# RF_Glow_Stick.net
KiCad netlist of a schematic drawn in EAGLE
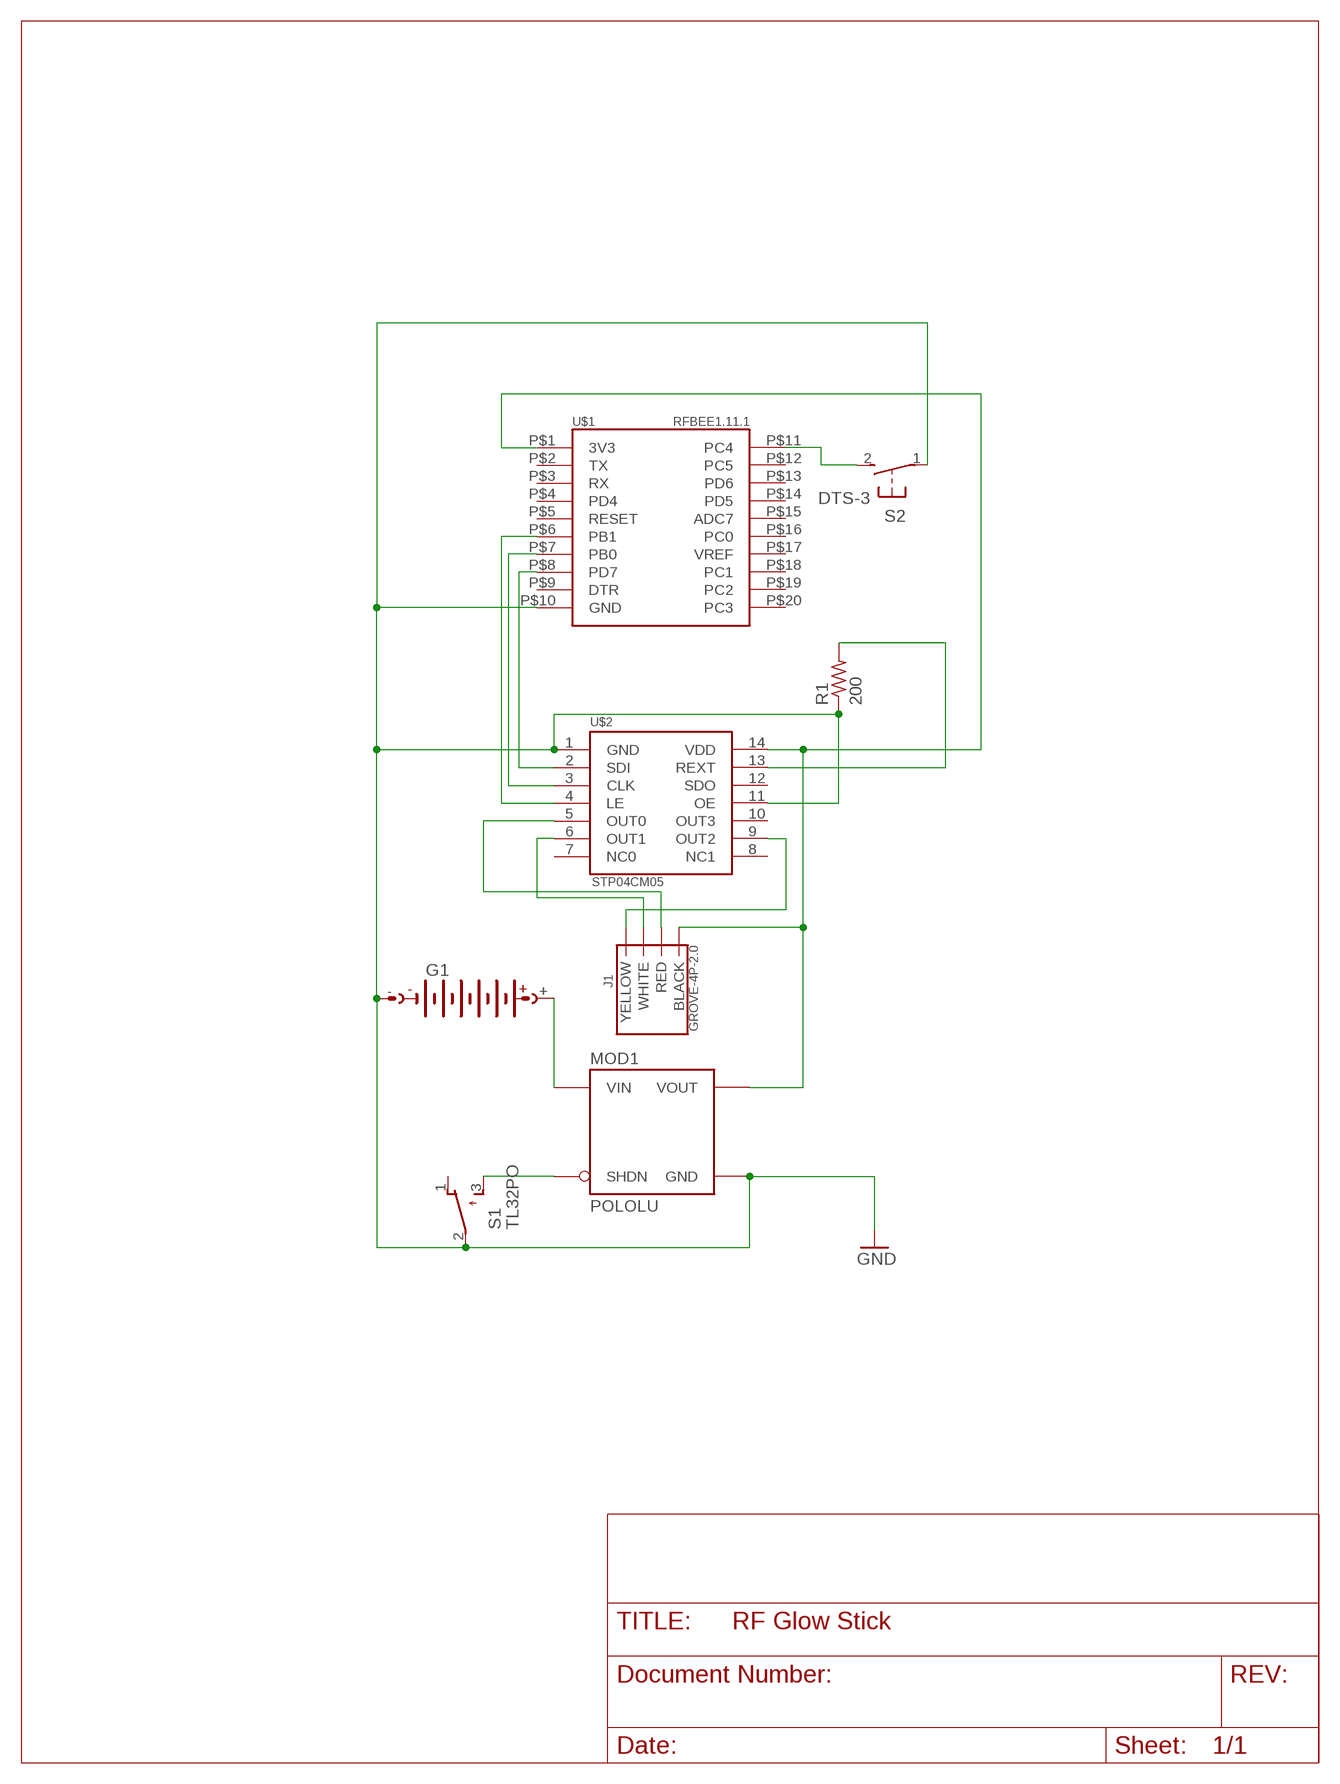
[diagram p0: schematic, sheet 1]

(export (version "E")
  (design (tool "Eeschema 10.0.6"))
  (components
    (comp (ref "G1")
      (value "AB9V")
      (footprint "eagle-import:AB9V")
      (libsource (lib "eagle-import") (part "AB9V"))
    )
    (comp (ref "J1")
      (value "GROVE-4P-2.0")
      (footprint "eagle-import:4P-2.0-90D")
      (libsource (lib "eagle-import") (part "GROVE-4P-2.0"))
    )
    (comp (ref "MOD1")
      (value "POLOLU")
      (footprint "eagle-import:POLOLU_REG09B")
      (libsource (lib "eagle-import") (part "POLOLU_REG09BV"))
    )
    (comp (ref "R1")
      (value "200")
      (footprint "eagle-import:0309_12")
      (libsource (lib "eagle-import") (part "R-US_0309/12"))
    )
    (comp (ref "S1")
      (value "TL32PO")
      (footprint "eagle-import:TL3XPO")
      (libsource (lib "eagle-import") (part "TL32PO"))
    )
    (comp (ref "S2")
      (value "DTS-3")
      (footprint "eagle-import:DTS-3")
      (libsource (lib "eagle-import") (part "DTS-3"))
    )
    (comp (ref "U$1")
      (value "RFBEE1.11.1")
      (footprint "eagle-import:RFBEE")
      (libsource (lib "eagle-import") (part "RFBEE1.11.1"))
    )
    (comp (ref "U$2")
      (value "STP04CM05")
      (footprint "eagle-import:DIL14")
      (libsource (lib "eagle-import") (part "STP04CM05STP04CM05"))
    )
  )
  (nets
    (net (code "1") (name "GND") (class "Default")
      (node (ref "G1") (pin "-") (pinfunction "-_-") (pintype "passive"))
      (node (ref "MOD1") (pin "G") (pinfunction "GND_G") (pintype "power_in"))
      (node (ref "R1") (pin "1") (pinfunction "1_1") (pintype "passive"))
      (node (ref "S1") (pin "2") (pinfunction "P_2") (pintype "passive"))
      (node (ref "S2") (pin "1") (pinfunction "1_1") (pintype "passive"))
      (node (ref "U$1") (pin "P$10") (pinfunction "GND_P$10") (pintype "bidirectional"))
      (node (ref "U$2") (pin "1") (pinfunction "GND_1") (pintype "bidirectional"))
      (node (ref "U$2") (pin "11") (pinfunction "OE_11") (pintype "bidirectional"))
    )
    (net (code "2") (name "Net-(MOD1-SHDN)") (class "Default")
      (node (ref "MOD1") (pin "S") (pinfunction "SHDN_S") (pintype "input"))
      (node (ref "S1") (pin "3") (pinfunction "S_3") (pintype "passive"))
    )
    (net (code "3") (name "Net-(MOD1-VIN)") (class "Default")
      (node (ref "G1") (pin "+") (pinfunction "+_+") (pintype "passive"))
      (node (ref "MOD1") (pin "I") (pinfunction "VIN_I") (pintype "power_in"))
    )
    (net (code "4") (name "Net-(MOD1-VOUT)") (class "Default")
      (node (ref "J1") (pin "BLACK") (pinfunction "BLACK_BLACK") (pintype "bidirectional"))
      (node (ref "MOD1") (pin "O") (pinfunction "VOUT_O") (pintype "output"))
      (node (ref "U$1") (pin "P$1") (pinfunction "3V3_P$1") (pintype "bidirectional"))
      (node (ref "U$2") (pin "14") (pinfunction "VDD_14") (pintype "bidirectional"))
    )
    (net (code "5") (name "Net-(U$1-PB0)") (class "Default")
      (node (ref "U$1") (pin "P$7") (pinfunction "PB0_P$7") (pintype "bidirectional"))
      (node (ref "U$2") (pin "3") (pinfunction "CLK_3") (pintype "bidirectional"))
    )
    (net (code "6") (name "Net-(U$1-PB1)") (class "Default")
      (node (ref "U$1") (pin "P$6") (pinfunction "PB1_P$6") (pintype "bidirectional"))
      (node (ref "U$2") (pin "4") (pinfunction "LE_4") (pintype "bidirectional"))
    )
    (net (code "7") (name "Net-(U$1-PC4)") (class "Default")
      (node (ref "S2") (pin "2") (pinfunction "2_2") (pintype "passive"))
      (node (ref "U$1") (pin "P$11") (pinfunction "PC4_P$11") (pintype "bidirectional"))
    )
    (net (code "8") (name "Net-(U$1-PD7)") (class "Default")
      (node (ref "U$1") (pin "P$8") (pinfunction "PD7_P$8") (pintype "bidirectional"))
      (node (ref "U$2") (pin "2") (pinfunction "SDI_2") (pintype "bidirectional"))
    )
    (net (code "9") (name "Net-(U$2-OUT0)") (class "Default")
      (node (ref "J1") (pin "RED") (pinfunction "RED_RED") (pintype "bidirectional"))
      (node (ref "U$2") (pin "5") (pinfunction "OUT0_5") (pintype "bidirectional"))
    )
    (net (code "10") (name "Net-(U$2-OUT1)") (class "Default")
      (node (ref "J1") (pin "WHITE") (pinfunction "WHITE_WHITE") (pintype "bidirectional"))
      (node (ref "U$2") (pin "6") (pinfunction "OUT1_6") (pintype "bidirectional"))
    )
    (net (code "11") (name "Net-(U$2-OUT2)") (class "Default")
      (node (ref "J1") (pin "YELLOW") (pinfunction "YELLOW_YELLOW") (pintype "bidirectional"))
      (node (ref "U$2") (pin "9") (pinfunction "OUT2_9") (pintype "bidirectional"))
    )
    (net (code "12") (name "Net-(U$2-REXT)") (class "Default")
      (node (ref "R1") (pin "2") (pinfunction "2_2") (pintype "passive"))
      (node (ref "U$2") (pin "13") (pinfunction "REXT_13") (pintype "bidirectional"))
    )
    (net (code "13") (name "unconnected-(S1-O-Pad1)") (class "Default")
      (node (ref "S1") (pin "1") (pinfunction "O_1") (pintype "passive"))
    )
    (net (code "14") (name "unconnected-(U$1-ADC7-PadP$15)") (class "Default")
      (node (ref "U$1") (pin "P$15") (pinfunction "ADC7_P$15") (pintype "bidirectional"))
    )
    (net (code "15") (name "unconnected-(U$1-DTR-PadP$9)") (class "Default")
      (node (ref "U$1") (pin "P$9") (pinfunction "DTR_P$9") (pintype "bidirectional"))
    )
    (net (code "16") (name "unconnected-(U$1-PC0-PadP$16)") (class "Default")
      (node (ref "U$1") (pin "P$16") (pinfunction "PC0_P$16") (pintype "bidirectional"))
    )
    (net (code "17") (name "unconnected-(U$1-PC1-PadP$18)") (class "Default")
      (node (ref "U$1") (pin "P$18") (pinfunction "PC1_P$18") (pintype "bidirectional"))
    )
    (net (code "18") (name "unconnected-(U$1-PC2-PadP$19)") (class "Default")
      (node (ref "U$1") (pin "P$19") (pinfunction "PC2_P$19") (pintype "bidirectional"))
    )
    (net (code "19") (name "unconnected-(U$1-PC3-PadP$20)") (class "Default")
      (node (ref "U$1") (pin "P$20") (pinfunction "PC3_P$20") (pintype "bidirectional"))
    )
    (net (code "20") (name "unconnected-(U$1-PC5-PadP$12)") (class "Default")
      (node (ref "U$1") (pin "P$12") (pinfunction "PC5_P$12") (pintype "bidirectional"))
    )
    (net (code "21") (name "unconnected-(U$1-PD4-PadP$4)") (class "Default")
      (node (ref "U$1") (pin "P$4") (pinfunction "PD4_P$4") (pintype "bidirectional"))
    )
    (net (code "22") (name "unconnected-(U$1-PD5-PadP$14)") (class "Default")
      (node (ref "U$1") (pin "P$14") (pinfunction "PD5_P$14") (pintype "bidirectional"))
    )
    (net (code "23") (name "unconnected-(U$1-PD6-PadP$13)") (class "Default")
      (node (ref "U$1") (pin "P$13") (pinfunction "PD6_P$13") (pintype "bidirectional"))
    )
    (net (code "24") (name "unconnected-(U$1-RESET-PadP$5)") (class "Default")
      (node (ref "U$1") (pin "P$5") (pinfunction "RESET_P$5") (pintype "bidirectional"))
    )
    (net (code "25") (name "unconnected-(U$1-RX-PadP$3)") (class "Default")
      (node (ref "U$1") (pin "P$3") (pinfunction "RX_P$3") (pintype "bidirectional"))
    )
    (net (code "26") (name "unconnected-(U$1-TX-PadP$2)") (class "Default")
      (node (ref "U$1") (pin "P$2") (pinfunction "TX_P$2") (pintype "bidirectional"))
    )
    (net (code "27") (name "unconnected-(U$1-VREF-PadP$17)") (class "Default")
      (node (ref "U$1") (pin "P$17") (pinfunction "VREF_P$17") (pintype "bidirectional"))
    )
    (net (code "28") (name "unconnected-(U$2-NC0-Pad7)") (class "Default")
      (node (ref "U$2") (pin "7") (pinfunction "NC0_7") (pintype "bidirectional"))
    )
    (net (code "29") (name "unconnected-(U$2-NC1-Pad8)") (class "Default")
      (node (ref "U$2") (pin "8") (pinfunction "NC1_8") (pintype "bidirectional"))
    )
    (net (code "30") (name "unconnected-(U$2-OUT3-Pad10)") (class "Default")
      (node (ref "U$2") (pin "10") (pinfunction "OUT3_10") (pintype "bidirectional"))
    )
    (net (code "31") (name "unconnected-(U$2-SDO-Pad12)") (class "Default")
      (node (ref "U$2") (pin "12") (pinfunction "SDO_12") (pintype "bidirectional"))
    )
  )
)
